# proprj_esp_s3_crokpocket_2025-06-12.net
KiCad netlist of a schematic drawn in EasyEDA Pro
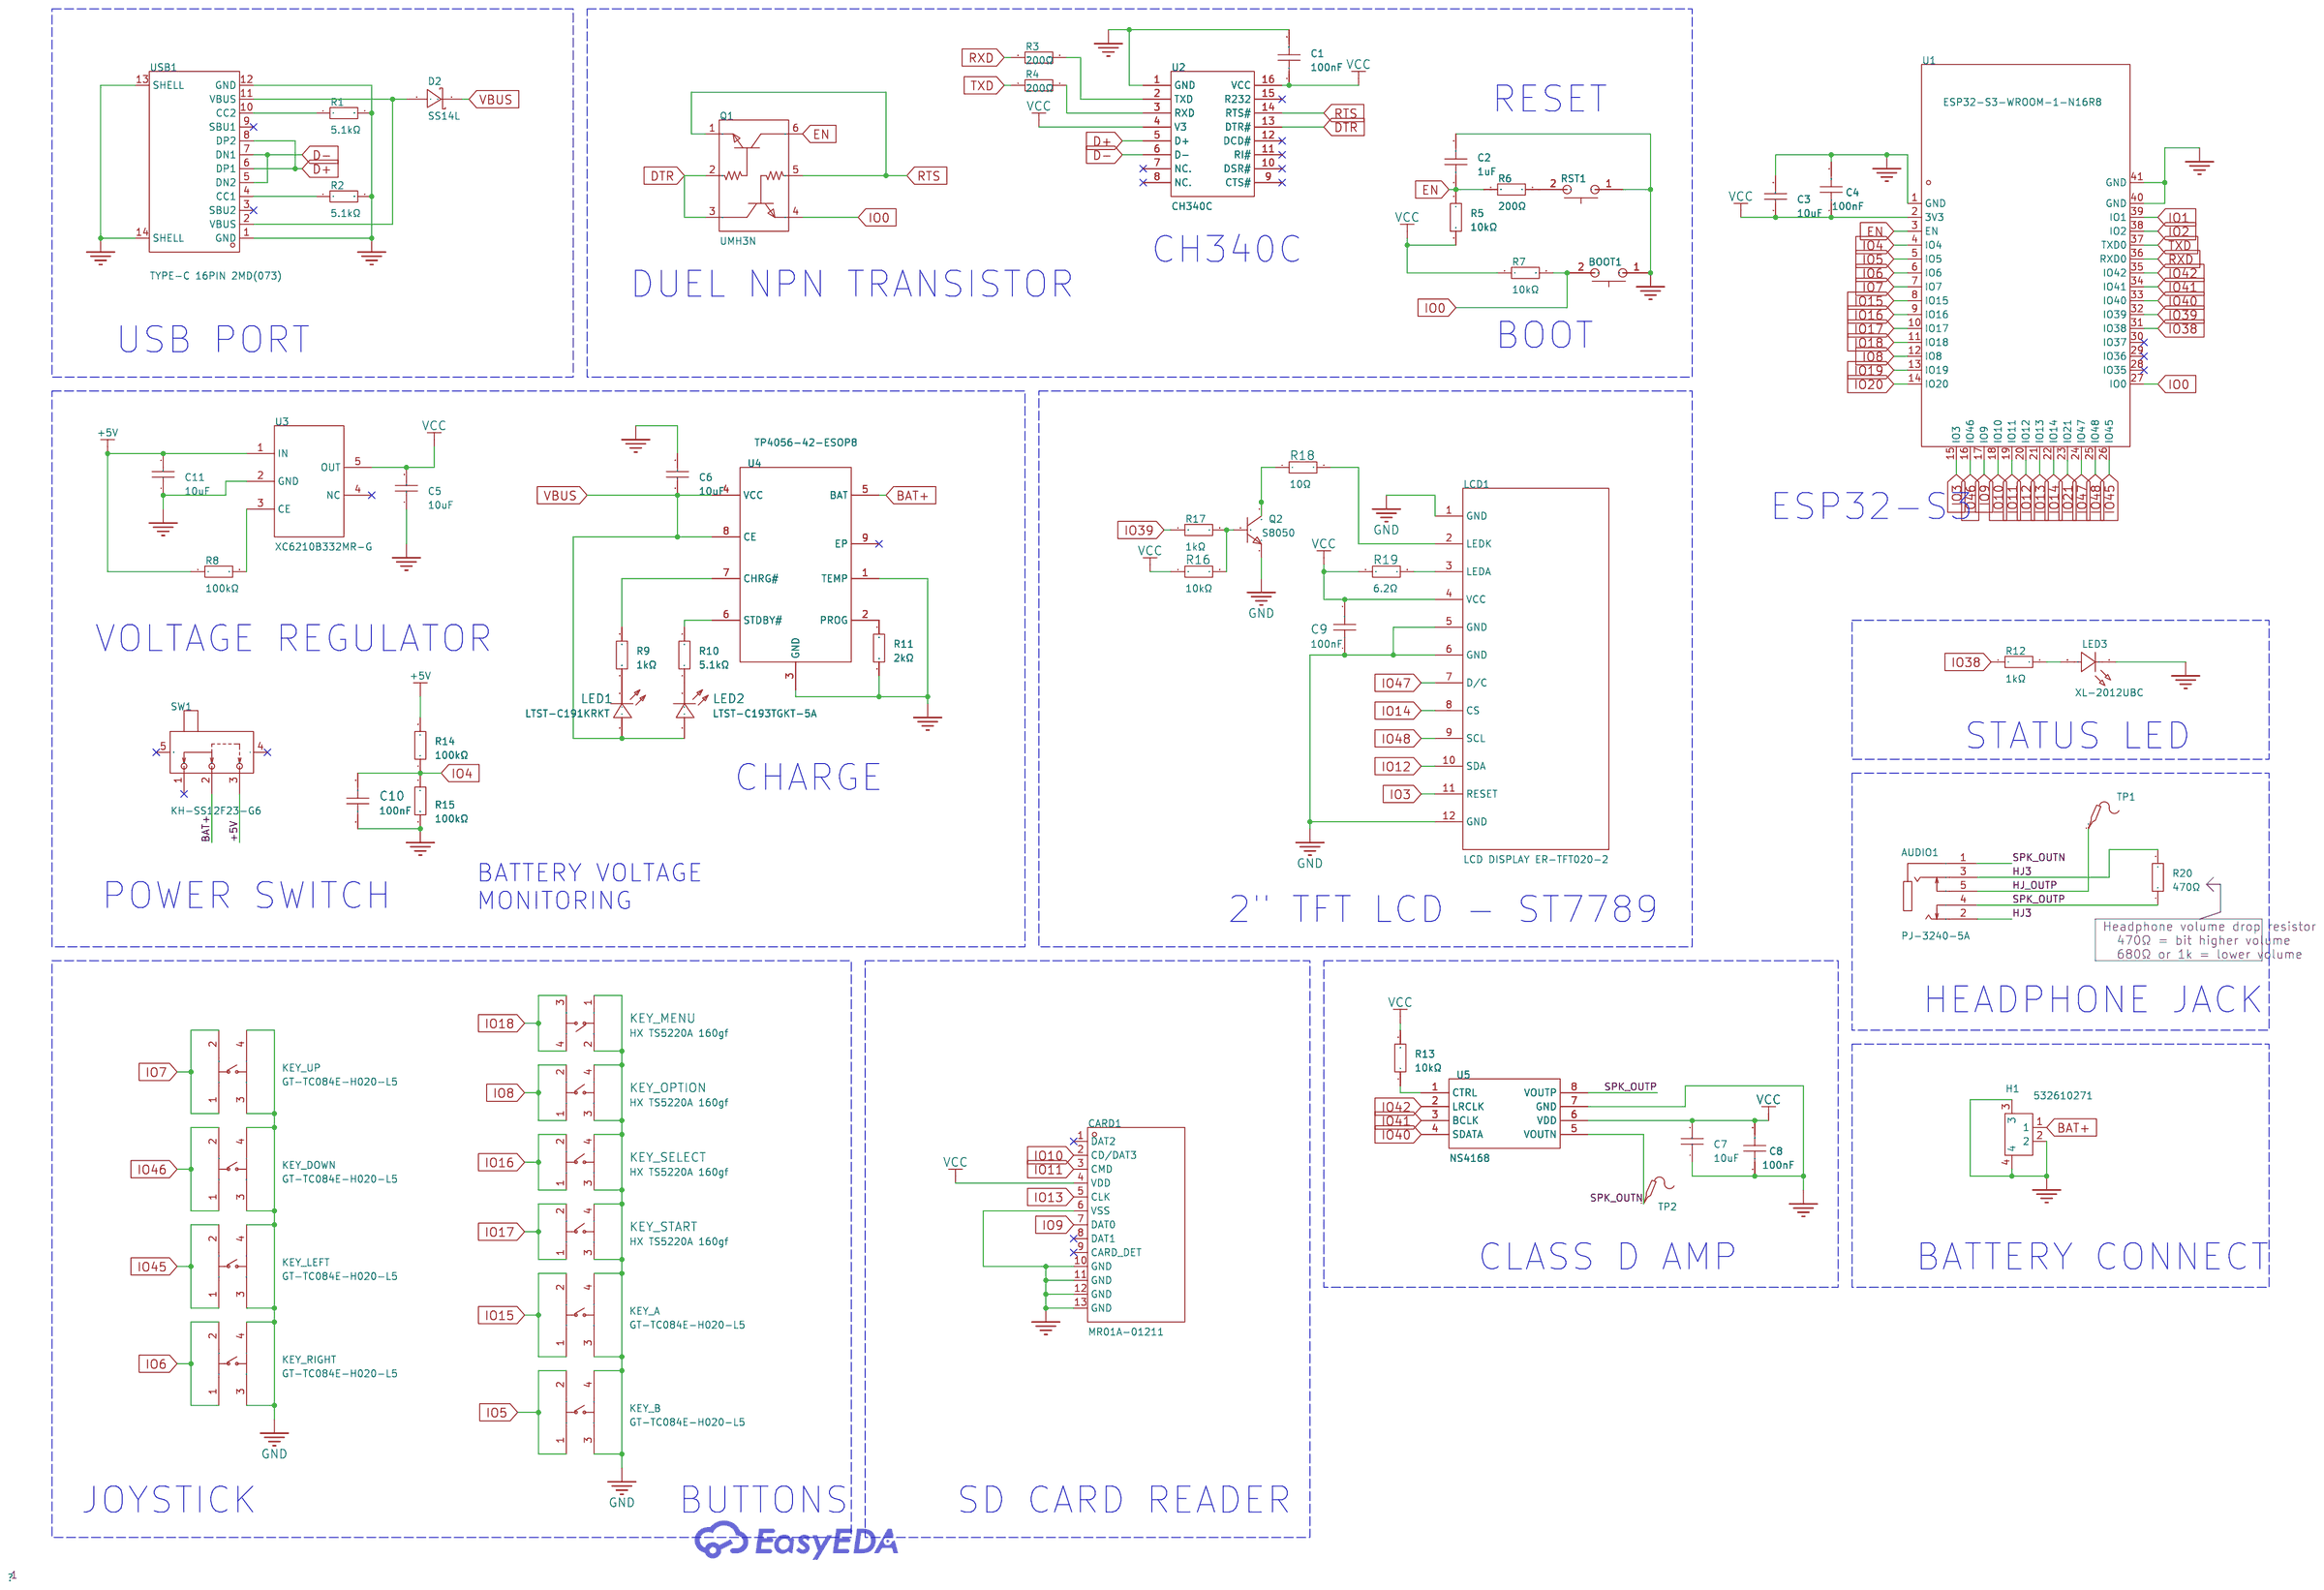
[diagram p0: schematic sheet]

(export (version "E")
  (design (tool "Eeschema 10.0.6"))
  (components
    (comp (ref "AUDIO1")
      (value "PJ-3240-5A")
      (footprint "easyedapro:AUDIO-TH_PJ-3240-5A")
      (description "Connector Type:3.5mm耳机座 Current Rating (Max):500mA Voltage Rating (Max):30V")
      (fields (field (name "Manufacturer") "韩国韩荣"))
      (libsource (lib "easyedapro") (part "PJ-3240-5A"))
    )
    (comp (ref "BOOT1")
      (value "GT-TC029B-H025-L1N")
      (footprint "easyedapro:SW-SMD_L3.9-W3.0-P4.45")
      (description "触点电流:50mA;额定电压(DC):12V;绝缘电阻:100MΩ;电路结构:单刀单掷;安装方式:立贴;带灯:无;作用力:250gf@±30gf;机械寿命:10万次;带支架:否;")
      (fields (field (name "Manufacturer") "G-Switch(品赞)"))
      (libsource (lib "easyedapro") (part "GT-TC029B-H025-L1N"))
    )
    (comp (ref "C1")
      (value "100nF")
      (footprint "easyedapro:C0603")
      (description "容值:100nF;精度:±10%;额定电压:50V;材质(温度系数):X7R;")
      (fields
        (field (name "Manufacturer Part") "CC0603KRX7R9BB104")
        (field (name "Manufacturer") "YAGEO(国巨)")
      )
      (libsource (lib "easyedapro") (part "CC0603KRX7R9BB104"))
    )
    (comp (ref "C2")
      (value "1uF")
      (footprint "easyedapro:C0603")
      (fields
        (field (name "Manufacturer Part") "CL10B105KA8NNNC")
        (field (name "Manufacturer") "SAMSUNG(三星)")
      )
      (libsource (lib "easyedapro") (part "CL10A105KB8NNNC"))
    )
    (comp (ref "C3")
      (value "10uF")
      (footprint "easyedapro:C0805")
      (fields
        (field (name "Manufacturer Part") "CL21B106KPQNNNE")
        (field (name "Manufacturer") "SAMSUNG(三星)")
      )
      (libsource (lib "easyedapro") (part "CL21B106KPQNNNE"))
    )
    (comp (ref "C4")
      (value "100nF")
      (footprint "easyedapro:C0603")
      (description "容值:100nF;精度:±10%;额定电压:50V;材质(温度系数):X7R;")
      (fields
        (field (name "Manufacturer Part") "CC0603KRX7R9BB104")
        (field (name "Manufacturer") "YAGEO(国巨)")
      )
      (libsource (lib "easyedapro") (part "CC0603KRX7R9BB104"))
    )
    (comp (ref "C5")
      (value "10uF")
      (footprint "easyedapro:C0805")
      (fields
        (field (name "Manufacturer Part") "CL21B106KPQNNNE")
        (field (name "Manufacturer") "SAMSUNG(三星)")
      )
      (libsource (lib "easyedapro") (part "CL21B106KPQNNNE"))
    )
    (comp (ref "C6")
      (value "10uF")
      (footprint "easyedapro:C0805")
      (fields
        (field (name "Manufacturer Part") "CL21B106KPQNNNE")
        (field (name "Manufacturer") "SAMSUNG(三星)")
      )
      (libsource (lib "easyedapro") (part "CL21B106KPQNNNE"))
    )
    (comp (ref "C7")
      (value "10uF")
      (footprint "easyedapro:C0805")
      (fields
        (field (name "Manufacturer Part") "CL21B106KPQNNNE")
        (field (name "Manufacturer") "SAMSUNG(三星)")
      )
      (libsource (lib "easyedapro") (part "CL21B106KPQNNNE"))
    )
    (comp (ref "C8")
      (value "100nF")
      (footprint "easyedapro:C0603")
      (description "容值:100nF;精度:±10%;额定电压:50V;材质(温度系数):X7R;")
      (fields
        (field (name "Manufacturer Part") "CC0603KRX7R9BB104")
        (field (name "Manufacturer") "YAGEO(国巨)")
      )
      (libsource (lib "easyedapro") (part "CC0603KRX7R9BB104"))
    )
    (comp (ref "C9")
      (value "100nF")
      (footprint "easyedapro:C0603")
      (fields
        (field (name "Manufacturer Part") "CC0603KRX7R9BB104")
        (field (name "Manufacturer") "YAGEO(国巨)")
      )
      (libsource (lib "") (part "CC0603KRX7R9BB104_1"))
    )
    (comp (ref "C10")
      (value "100nF")
      (footprint "easyedapro:C0603")
      (fields
        (field (name "Manufacturer Part") "CC0603KRX7R9BB104")
        (field (name "Manufacturer") "YAGEO(国巨)")
      )
      (libsource (lib "") (part "CC0603KRX7R9BB104_1"))
    )
    (comp (ref "C11")
      (value "10uF")
      (footprint "easyedapro:C0805")
      (fields
        (field (name "Manufacturer Part") "CL21B106KPQNNNE")
        (field (name "Manufacturer") "SAMSUNG(三星)")
      )
      (libsource (lib "easyedapro") (part "CL21B106KPQNNNE"))
    )
    (comp (ref "CARD1")
      (value "MR01A-01211")
      (footprint "easyedapro:TF-SMD_MR01A-01211")
      (description "卡类型:MicroSD卡(TF卡);连接器类型:卡座;卡连接方式:自弹式;本体最大高度:1.85mm;工作温度范围:-25°C~+85°C;")
      (fields (field (name "Manufacturer") "ATOM(爱特姆)"))
      (libsource (lib "easyedapro") (part "MR01A-01211"))
    )
    (comp (ref "D2")
      (value "SS14L")
      (footprint "easyedapro:SOD-123F_L2.8-W1.8-LS3.7-RD")
      (description "直流反向耐压(Vr):40V;平均整流电流(Io):1A;正向压降(Vf):550mV 1A;")
      (fields (field (name "Manufacturer") "Hottech(合科泰)"))
      (libsource (lib "easyedapro") (part "SS14L_C190475"))
    )
    (comp (ref "H1")
      (value "532610271")
      (footprint "easyedapro:CONN-SMD_532610271")
      (fields (field (name "Manufacturer") "MOLEX"))
      (libsource (lib "easyedapro") (part "532610271_C177225"))
    )
    (comp (ref "KEY_A")
      (value "GT-TC084E-H020-L5")
      (footprint "easyedapro:SW-SMD_4P-L5.2-W5.2-P3.70-LS6.4")
      (fields (field (name "Manufacturer") "G-Switch(品赞)"))
      (libsource (lib "easyedapro") (part "GT-TC084E-H020-L5"))
    )
    (comp (ref "KEY_B")
      (value "GT-TC084E-H020-L5")
      (footprint "easyedapro:SW-SMD_4P-L5.2-W5.2-P3.70-LS6.4")
      (fields (field (name "Manufacturer") "G-Switch(品赞)"))
      (libsource (lib "easyedapro") (part "GT-TC084E-H020-L5"))
    )
    (comp (ref "KEY_DOWN")
      (value "GT-TC084E-H020-L5")
      (footprint "easyedapro:SW-SMD_4P-L5.2-W5.2-P3.70-LS6.4")
      (fields (field (name "Manufacturer") "G-Switch(品赞)"))
      (libsource (lib "easyedapro") (part "GT-TC084E-H020-L5"))
    )
    (comp (ref "KEY_LEFT")
      (value "GT-TC084E-H020-L5")
      (footprint "easyedapro:SW-SMD_4P-L5.2-W5.2-P3.70-LS6.4")
      (fields (field (name "Manufacturer") "G-Switch(品赞)"))
      (libsource (lib "easyedapro") (part "GT-TC084E-H020-L5"))
    )
    (comp (ref "KEY_MENU")
      (value "HX TS5220A 160gf")
      (footprint "easyedapro:SW-SMD_4P-L5.2-W5.2-P3.70-LS6.4")
      (fields (field (name "Manufacturer") "hanxia(韩下)"))
      (libsource (lib "easyedapro") (part "HX TS5220A 160GF"))
    )
    (comp (ref "KEY_OPTION")
      (value "HX TS5220A 160gf")
      (footprint "easyedapro:SW-SMD_4P-L5.2-W5.2-P3.70-LS6.4")
      (fields (field (name "Manufacturer") "hanxia(韩下)"))
      (libsource (lib "easyedapro") (part "HX TS5220A 160GF"))
    )
    (comp (ref "KEY_RIGHT")
      (value "GT-TC084E-H020-L5")
      (footprint "easyedapro:SW-SMD_4P-L5.2-W5.2-P3.70-LS6.4")
      (fields (field (name "Manufacturer") "G-Switch(品赞)"))
      (libsource (lib "easyedapro") (part "GT-TC084E-H020-L5"))
    )
    (comp (ref "KEY_SELECT")
      (value "HX TS5220A 160gf")
      (footprint "easyedapro:SW-SMD_4P-L5.2-W5.2-P3.70-LS6.4")
      (fields (field (name "Manufacturer") "hanxia(韩下)"))
      (libsource (lib "easyedapro") (part "HX TS5220A 160GF"))
    )
    (comp (ref "KEY_START")
      (value "HX TS5220A 160gf")
      (footprint "easyedapro:SW-SMD_4P-L5.2-W5.2-P3.70-LS6.4")
      (fields (field (name "Manufacturer") "hanxia(韩下)"))
      (libsource (lib "easyedapro") (part "HX TS5220A 160GF"))
    )
    (comp (ref "KEY_UP")
      (value "GT-TC084E-H020-L5")
      (footprint "easyedapro:SW-SMD_4P-L5.2-W5.2-P3.70-LS6.4")
      (fields (field (name "Manufacturer") "G-Switch(品赞)"))
      (libsource (lib "easyedapro") (part "GT-TC084E-H020-L5"))
    )
    (comp (ref "LCD1")
      (value "LCD DISPLAY ER-TFT020-2")
      (fields (field (name "Manufacturer Part") "ER-TFT020-2") (field (name "Manufacturer") "EastRising"))
      (libsource (lib "easyedapro") (part "LCD DISPLAY ER-TFT020-2"))
    )
    (comp (ref "LED1")
      (value "LTST-C191KRKT")
      (footprint "easyedapro:LED0603-RD")
      (fields (field (name "Manufacturer") "LITEON(光宝)"))
      (libsource (lib "easyedapro") (part "LTST-C191KRKT"))
    )
    (comp (ref "LED2")
      (value "LTST-C193TGKT-5A")
      (footprint "easyedapro:LED0603-RD")
      (fields (field (name "Manufacturer") "LITEON(光宝)"))
      (libsource (lib "easyedapro") (part "LTST-C193TGKT-5A"))
    )
    (comp (ref "LED3")
      (value "XL-2012UBC")
      (footprint "easyedapro:LED0805-RD")
      (description "发光颜色:蓝色;功率:80mW;正向电流:25mA;主波长:460nm~469nm;透镜颜色:无色透明透镜;色温:-;发光角度:120°;载带方式:正贴;工作温度:-30°C~+85°C;")
      (fields (field (name "Manufacturer") "XINGLIGHT(成兴光)"))
      (libsource (lib "easyedapro") (part "XL-2012UBC"))
    )
    (comp (ref "Q1")
      (value "UMH3N")
      (footprint "easyedapro:SC-70-6_L2.2-W1.3-P0.65-LS2.1-BR")
      (description "晶体管类型:2个NPN-预偏置;功率(Pd):150mW;集电极电流(Ic):100mA;集射极击穿电压(Vceo):50V;")
      (fields (field (name "Manufacturer") "CJ(江苏长电/长晶)"))
      (libsource (lib "easyedapro") (part "UMH3N"))
    )
    (comp (ref "Q2")
      (value "S8050")
      (footprint "easyedapro:SOT-23-3_L2.9-W1.6-P1.90-LS2.8-BR")
      (fields (field (name "Manufacturer") "Hottech(合科泰)"))
      (libsource (lib "easyedapro") (part "S8050_C181158"))
    )
    (comp (ref "R1")
      (value "5.1kΩ")
      (footprint "easyedapro:R0603")
      (description "电阻类型:厚膜电阻;阻值:5.1kΩ;精度:±1%;功率:100mW;最大工作电压:75V;温度系数:±100ppm/°C;")
      (fields
        (field (name "Manufacturer Part") "0603WAF5101T5E")
        (field (name "Manufacturer") "UNI-ROYAL(厚声)")
      )
      (libsource (lib "easyedapro") (part "0603WAF5101T5E"))
    )
    (comp (ref "R2")
      (value "5.1kΩ")
      (footprint "easyedapro:R0603")
      (description "电阻类型:厚膜电阻;阻值:5.1kΩ;精度:±1%;功率:100mW;最大工作电压:75V;温度系数:±100ppm/°C;")
      (fields
        (field (name "Manufacturer Part") "0603WAF5101T5E")
        (field (name "Manufacturer") "UNI-ROYAL(厚声)")
      )
      (libsource (lib "easyedapro") (part "0603WAF5101T5E"))
    )
    (comp (ref "R3")
      (value "200Ω")
      (footprint "easyedapro:R0603")
      (description "电阻类型:厚膜电阻;阻值:200Ω;精度:±1%;功率:100mW;最大工作电压:75V;温度系数:±100ppm/°C;")
      (fields
        (field (name "Manufacturer Part") "0603WAF2000T5E")
        (field (name "Manufacturer") "UNI-ROYAL(厚声)")
      )
      (libsource (lib "easyedapro") (part "0603WAF2000T5E"))
    )
    (comp (ref "R4")
      (value "200Ω")
      (footprint "easyedapro:R0603")
      (description "电阻类型:厚膜电阻;阻值:200Ω;精度:±1%;功率:100mW;最大工作电压:75V;温度系数:±100ppm/°C;")
      (fields
        (field (name "Manufacturer Part") "0603WAF2000T5E")
        (field (name "Manufacturer") "UNI-ROYAL(厚声)")
      )
      (libsource (lib "easyedapro") (part "0603WAF2000T5E"))
    )
    (comp (ref "R5")
      (value "10kΩ")
      (footprint "easyedapro:R0603")
      (description "电阻类型:厚膜电阻;阻值:10kΩ;精度:±1%;功率:100mW;最大工作电压:75V;温度系数:±100ppm/°C;")
      (fields
        (field (name "Manufacturer Part") "0603WAF1002T5E")
        (field (name "Manufacturer") "UNI-ROYAL(厚声)")
      )
      (libsource (lib "") (part "0603WAF1002T5E_1"))
    )
    (comp (ref "R6")
      (value "200Ω")
      (footprint "easyedapro:R0603")
      (description "电阻类型:厚膜电阻;阻值:200Ω;精度:±1%;功率:100mW;最大工作电压:75V;温度系数:±100ppm/°C;")
      (fields
        (field (name "Manufacturer Part") "0603WAF2000T5E")
        (field (name "Manufacturer") "UNI-ROYAL(厚声)")
      )
      (libsource (lib "easyedapro") (part "0603WAF2000T5E"))
    )
    (comp (ref "R7")
      (value "10kΩ")
      (footprint "easyedapro:R0603")
      (description "电阻类型:厚膜电阻;阻值:10kΩ;精度:±1%;功率:100mW;最大工作电压:75V;温度系数:±100ppm/°C;")
      (fields
        (field (name "Manufacturer Part") "0603WAF1002T5E")
        (field (name "Manufacturer") "UNI-ROYAL(厚声)")
      )
      (libsource (lib "") (part "0603WAF1002T5E_1"))
    )
    (comp (ref "R8")
      (value "100kΩ")
      (footprint "easyedapro:R0603")
      (fields
        (field (name "Manufacturer Part") "0603WAF1003T5E")
        (field (name "Manufacturer") "UNI-ROYAL(厚声)")
      )
      (libsource (lib "easyedapro") (part "0603WAF1003T5E"))
    )
    (comp (ref "R9")
      (value "1kΩ")
      (footprint "easyedapro:R0603")
      (description "电阻类型:厚膜电阻;阻值:1kΩ;精度:±1%;功率:100mW;最大工作电压:75V;温度系数:±100ppm/°C;")
      (fields
        (field (name "Manufacturer Part") "0603WAF1001T5E")
        (field (name "Manufacturer") "UNI-ROYAL(厚声)")
      )
      (libsource (lib "easyedapro") (part "0603WAF1001T5E"))
    )
    (comp (ref "R10")
      (value "5.1kΩ")
      (footprint "easyedapro:R0603")
      (fields
        (field (name "Manufacturer Part") "0603WAF5101T5E")
        (field (name "Manufacturer") "UNI-ROYAL(厚声)")
      )
      (libsource (lib "easyedapro") (part "0603WAF5101T5E"))
    )
    (comp (ref "R11")
      (value "2kΩ")
      (footprint "easyedapro:R0603")
      (description "电阻类型:厚膜电阻;阻值:2kΩ;精度:±1%;功率:100mW;最大工作电压:75V;温度系数:±100ppm/°C;")
      (fields
        (field (name "Manufacturer Part") "0603WAF2001T5E")
        (field (name "Manufacturer") "UNI-ROYAL(厚声)")
      )
      (libsource (lib "easyedapro") (part "0603WAF2001T5E"))
    )
    (comp (ref "R12")
      (value "1kΩ")
      (footprint "easyedapro:R0603")
      (description "电阻类型:厚膜电阻;阻值:1kΩ;精度:±1%;功率:100mW;最大工作电压:75V;温度系数:±100ppm/°C;")
      (fields
        (field (name "Manufacturer Part") "0603WAF1001T5E")
        (field (name "Manufacturer") "UNI-ROYAL(厚声)")
      )
      (libsource (lib "easyedapro") (part "0603WAF1001T5E"))
    )
    (comp (ref "R13")
      (value "10kΩ")
      (footprint "easyedapro:R0603")
      (description "电阻类型:厚膜电阻;阻值:10kΩ;精度:±1%;功率:100mW;最大工作电压:75V;温度系数:±100ppm/°C;")
      (fields
        (field (name "Manufacturer Part") "0603WAF1002T5E")
        (field (name "Manufacturer") "UNI-ROYAL(厚声)")
      )
      (libsource (lib "") (part "0603WAF1002T5E_1"))
    )
    (comp (ref "R14")
      (value "100kΩ")
      (footprint "easyedapro:R0603")
      (fields
        (field (name "Manufacturer Part") "0603WAF1003T5E")
        (field (name "Manufacturer") "UNI-ROYAL(厚声)")
      )
      (libsource (lib "easyedapro") (part "0603WAF1003T5E"))
    )
    (comp (ref "R15")
      (value "100kΩ")
      (footprint "easyedapro:R0603")
      (fields
        (field (name "Manufacturer Part") "0603WAF1003T5E")
        (field (name "Manufacturer") "UNI-ROYAL(厚声)")
      )
      (libsource (lib "easyedapro") (part "0603WAF1003T5E"))
    )
    (comp (ref "R16")
      (value "10kΩ")
      (footprint "easyedapro:R0603")
      (fields
        (field (name "Manufacturer Part") "0603WAF1002T5E")
        (field (name "Manufacturer") "UNI-ROYAL(厚声)")
      )
      (libsource (lib "easyedapro") (part "0603WAF1002T5E"))
    )
    (comp (ref "R17")
      (value "1kΩ")
      (footprint "easyedapro:R0603")
      (fields
        (field (name "Manufacturer Part") "0603WAF1001T5E")
        (field (name "Manufacturer") "UNI-ROYAL(厚声)")
      )
      (libsource (lib "easyedapro") (part "0603WAF1001T5E"))
    )
    (comp (ref "R18")
      (value "10Ω")
      (footprint "easyedapro:R0603")
      (fields
        (field (name "Manufacturer Part") "0603WAF100JT5E")
        (field (name "Manufacturer") "UNI-ROYAL(厚声)")
      )
      (libsource (lib "easyedapro") (part "0603WAF100JT5E"))
    )
    (comp (ref "R19")
      (value "6.2Ω")
      (footprint "easyedapro:R0603")
      (fields
        (field (name "Manufacturer Part") "0603WAF620KT5E")
        (field (name "Manufacturer") "UNI-ROYAL(厚声)")
      )
      (libsource (lib "easyedapro") (part "0603WAF620KT5E"))
    )
    (comp (ref "R20")
      (value "470Ω")
      (footprint "easyedapro:R0603")
      (fields
        (field (name "Manufacturer Part") "0603WAF4700T5E")
        (field (name "Manufacturer") "UNI-ROYAL(厚声)")
      )
      (libsource (lib "easyedapro") (part "0603WAF4700T5E"))
    )
    (comp (ref "RST1")
      (value "GT-TC029B-H025-L1N")
      (footprint "easyedapro:SW-SMD_L3.9-W3.0-P4.45")
      (description "触点电流:50mA;额定电压(DC):12V;绝缘电阻:100MΩ;电路结构:单刀单掷;安装方式:立贴;带灯:无;作用力:250gf@±30gf;机械寿命:10万次;带支架:否;")
      (fields (field (name "Manufacturer") "G-Switch(品赞)"))
      (libsource (lib "easyedapro") (part "GT-TC029B-H025-L1N"))
    )
    (comp (ref "SW1")
      (value "KH-SS12F23-G6")
      (footprint "easyedapro:SW-TH_KH-SS12F23-G6")
      (fields (field (name "Manufacturer") "kinghelm(金航标)"))
      (libsource (lib "easyedapro") (part "KH-SS12F23-G6"))
    )
    (comp (ref "TP1")
      (value "~")
      (footprint "easyedapro:Test-Point-0.5mm")
      (description "Test Point 测试点")
      (libsource (lib "easyedapro") (part "Test-Point"))
    )
    (comp (ref "TP2")
      (value "~")
      (footprint "easyedapro:Test-Point-0.5mm")
      (description "Test Point 测试点")
      (libsource (lib "easyedapro") (part "Test-Point"))
    )
    (comp (ref "U1")
      (value "ESP32-S3-WROOM-1-N16R8")
      (footprint "easyedapro:WIRELM-SMD_ESP32-S3-WROOM-1")
      (fields (field (name "Manufacturer") "ESPRESSIF(乐鑫)"))
      (libsource (lib "easyedapro") (part "ESP32-S3-WROOM-1(N16R8)"))
    )
    (comp (ref "U2")
      (value "CH340C")
      (fields (field (name "Manufacturer") "WCH(南京沁恒)"))
      (libsource (lib "easyedapro") (part "CH340C"))
    )
    (comp (ref "U3")
      (value "XC6210B332MR-G")
      (footprint "easyedapro:SOT-23-5_L3.0-W1.7-P0.95-LS2.8-BR")
      (fields (field (name "Manufacturer") "TOREX(特瑞仕)"))
      (libsource (lib "easyedapro") (part "XC6210B332MR"))
    )
    (comp (ref "U4")
      (value "TP4056-42-ESOP8")
      (footprint "easyedapro:ESOP-8_L4.9-W3.9-P1.27-LS6.0-BL-EP")
      (fields (field (name "Manufacturer") "TOPPOWER(南京拓微)"))
      (libsource (lib "easyedapro") (part "TP4056"))
    )
    (comp (ref "U5")
      (value "NS4168")
      (footprint "easyedapro:ESOP-8_L4.9-W3.9-P1.27-LS6.0-BL-EP-1")
      (description "NS4168 2.5W I2S数字输入单声道D类音频功率放大器功放芯片IC")
      (libsource (lib "easyedapro") (part "NS4168"))
    )
    (comp (ref "USB1")
      (value "TYPE-C 16PIN 2MD(073)")
      (footprint "easyedapro:USB-C-SMD_TYPE-C-6PIN-2MD-073")
      (description "连接器类型:Type-C;标准:-;公母:母座;触点数量:16;端口数量:1;安装方式:卧贴;额定电流 - 电源:5A;工作温度范围:-25°C~+85°C;")
      (fields (field (name "Manufacturer") "SHOU HAN(首韩)"))
      (libsource (lib "easyedapro") (part "TYPE-C 16PIN 2MD(073)"))
    )
  )
  (nets
    (net (code "1") (name "+5V") (class "Default")
      (node (ref "C11") (pin "2") (pinfunction "2_2") (pintype "input"))
      (node (ref "R14") (pin "2") (pinfunction "2_2") (pintype "input"))
      (node (ref "R8") (pin "1") (pinfunction "1_1") (pintype "input"))
      (node (ref "SW1") (pin "3") (pinfunction "3_3") (pintype "unspecified"))
      (node (ref "U3") (pin "1") (pinfunction "IN_1") (pintype "unspecified"))
    )
    (net (code "2") (name "/HJ3") (class "Default")
      (node (ref "AUDIO1") (pin "2") (pinfunction "2_2") (pintype "unspecified"))
      (node (ref "AUDIO1") (pin "3") (pinfunction "3_3") (pintype "unspecified"))
      (node (ref "R20") (pin "2") (pinfunction "2_2") (pintype "input"))
    )
    (net (code "3") (name "/HJ_OUTP") (class "Default")
      (node (ref "AUDIO1") (pin "5") (pinfunction "5_5") (pintype "unspecified"))
      (node (ref "TP1") (pin "1") (pinfunction "1_1") (pintype "input"))
    )
    (net (code "4") (name "/SPK_OUTN") (class "Default")
      (node (ref "AUDIO1") (pin "1") (pinfunction "1_1") (pintype "unspecified"))
      (node (ref "TP2") (pin "1") (pinfunction "1_1") (pintype "input"))
      (node (ref "U5") (pin "5") (pinfunction "VOUTN_5") (pintype "input"))
    )
    (net (code "5") (name "/SPK_OUTP") (class "Default")
      (node (ref "AUDIO1") (pin "4") (pinfunction "4_4") (pintype "unspecified"))
      (node (ref "R20") (pin "1") (pinfunction "1_1") (pintype "input"))
      (node (ref "U5") (pin "8") (pinfunction "VOUTP_8") (pintype "input"))
    )
    (net (code "6") (name "BAT+") (class "Default")
      (node (ref "H1") (pin "1") (pinfunction "1_1") (pintype "unspecified"))
      (node (ref "SW1") (pin "2") (pinfunction "2_2") (pintype "unspecified"))
      (node (ref "U4") (pin "5") (pinfunction "BAT_5") (pintype "unspecified"))
    )
    (net (code "7") (name "D+") (class "Default")
      (node (ref "U2") (pin "5") (pinfunction "D+_5") (pintype "input"))
      (node (ref "USB1") (pin "6") (pinfunction "DP1_6") (pintype "input"))
      (node (ref "USB1") (pin "8") (pinfunction "DP2_8") (pintype "input"))
    )
    (net (code "8") (name "D-") (class "Default")
      (node (ref "U2") (pin "6") (pinfunction "D-_6") (pintype "input"))
      (node (ref "USB1") (pin "5") (pinfunction "DN2_5") (pintype "input"))
      (node (ref "USB1") (pin "7") (pinfunction "DN1_7") (pintype "input"))
    )
    (net (code "9") (name "DTR") (class "Default")
      (node (ref "Q1") (pin "2") (pinfunction "B_2") (pintype "input"))
      (node (ref "Q1") (pin "3") (pinfunction "C_3") (pintype "input"))
      (node (ref "U2") (pin "13") (pinfunction "DTR#_13") (pintype "input"))
    )
    (net (code "10") (name "EN") (class "Default")
      (node (ref "C2") (pin "1") (pinfunction "1_1") (pintype "unspecified"))
      (node (ref "Q1") (pin "6") (pinfunction "C_6") (pintype "input"))
      (node (ref "R5") (pin "1") (pinfunction "1_1") (pintype "input"))
      (node (ref "R6") (pin "2") (pinfunction "2_2") (pintype "input"))
      (node (ref "U1") (pin "3") (pinfunction "EN_3") (pintype "input"))
    )
    (net (code "11") (name "GND") (class "Default")
      (node (ref "BOOT1") (pin "1") (pinfunction "1_1") (pintype "input"))
      (node (ref "C1") (pin "2") (pinfunction "2_2") (pintype "unspecified"))
      (node (ref "C10") (pin "2") (pinfunction "2_2") (pintype "input"))
      (node (ref "C11") (pin "1") (pinfunction "1_1") (pintype "input"))
      (node (ref "C2") (pin "2") (pinfunction "2_2") (pintype "unspecified"))
      (node (ref "C3") (pin "2") (pinfunction "2_2") (pintype "input"))
      (node (ref "C4") (pin "2") (pinfunction "2_2") (pintype "unspecified"))
      (node (ref "C5") (pin "1") (pinfunction "1_1") (pintype "input"))
      (node (ref "C6") (pin "2") (pinfunction "2_2") (pintype "input"))
      (node (ref "C7") (pin "1") (pinfunction "1_1") (pintype "input"))
      (node (ref "C8") (pin "1") (pinfunction "1_1") (pintype "unspecified"))
      (node (ref "C9") (pin "1") (pinfunction "1_1") (pintype "input"))
      (node (ref "CARD1") (pin "10") (pinfunction "GND_10") (pintype "input"))
      (node (ref "CARD1") (pin "11") (pinfunction "GND_11") (pintype "input"))
      (node (ref "CARD1") (pin "12") (pinfunction "GND_12") (pintype "input"))
      (node (ref "CARD1") (pin "13") (pinfunction "GND_13") (pintype "input"))
      (node (ref "CARD1") (pin "6") (pinfunction "VSS_6") (pintype "input"))
      (node (ref "H1") (pin "2") (pinfunction "2_2") (pintype "unspecified"))
      (node (ref "H1") (pin "3") (pinfunction "3_3") (pintype "unspecified"))
      (node (ref "H1") (pin "4") (pinfunction "4_4") (pintype "unspecified"))
      (node (ref "KEY_A") (pin "3") (pinfunction "3_3") (pintype "unspecified"))
      (node (ref "KEY_A") (pin "4") (pinfunction "4_4") (pintype "unspecified"))
      (node (ref "KEY_B") (pin "3") (pinfunction "3_3") (pintype "unspecified"))
      (node (ref "KEY_B") (pin "4") (pinfunction "4_4") (pintype "unspecified"))
      (node (ref "KEY_DOWN") (pin "3") (pinfunction "3_3") (pintype "unspecified"))
      (node (ref "KEY_DOWN") (pin "4") (pinfunction "4_4") (pintype "unspecified"))
      (node (ref "KEY_LEFT") (pin "3") (pinfunction "3_3") (pintype "unspecified"))
      (node (ref "KEY_LEFT") (pin "4") (pinfunction "4_4") (pintype "unspecified"))
      (node (ref "KEY_MENU") (pin "1") (pinfunction "1_1") (pintype "input"))
      (node (ref "KEY_MENU") (pin "2") (pinfunction "2_2") (pintype "input"))
      (node (ref "KEY_OPTION") (pin "3") (pinfunction "3_3") (pintype "input"))
      (node (ref "KEY_OPTION") (pin "4") (pinfunction "4_4") (pintype "input"))
      (node (ref "KEY_RIGHT") (pin "3") (pinfunction "3_3") (pintype "unspecified"))
      (node (ref "KEY_RIGHT") (pin "4") (pinfunction "4_4") (pintype "unspecified"))
      (node (ref "KEY_SELECT") (pin "3") (pinfunction "3_3") (pintype "input"))
      (node (ref "KEY_SELECT") (pin "4") (pinfunction "4_4") (pintype "input"))
      (node (ref "KEY_START") (pin "3") (pinfunction "3_3") (pintype "input"))
      (node (ref "KEY_START") (pin "4") (pinfunction "4_4") (pintype "input"))
      (node (ref "KEY_UP") (pin "3") (pinfunction "3_3") (pintype "unspecified"))
      (node (ref "KEY_UP") (pin "4") (pinfunction "4_4") (pintype "unspecified"))
      (node (ref "LCD1") (pin "1") (pinfunction "GND_1") (pintype "unspecified"))
      (node (ref "LCD1") (pin "12") (pinfunction "GND_12") (pintype "unspecified"))
      (node (ref "LCD1") (pin "5") (pinfunction "GND_5") (pintype "unspecified"))
      (node (ref "LCD1") (pin "6") (pinfunction "GND_6") (pintype "unspecified"))
      (node (ref "LED3") (pin "1") (pinfunction "K_1") (pintype "unspecified"))
      (node (ref "Q2") (pin "2") (pinfunction "2_2") (pintype "input"))
      (node (ref "R1") (pin "2") (pinfunction "2_2") (pintype "input"))
      (node (ref "R11") (pin "1") (pinfunction "1_1") (pintype "input"))
      (node (ref "R15") (pin "2") (pinfunction "2_2") (pintype "input"))
      (node (ref "R2") (pin "2") (pinfunction "2_2") (pintype "input"))
      (node (ref "RST1") (pin "1") (pinfunction "1_1") (pintype "input"))
      (node (ref "U1") (pin "1") (pinfunction "GND_1") (pintype "input"))
      (node (ref "U1") (pin "40") (pinfunction "GND_40") (pintype "input"))
      (node (ref "U1") (pin "41") (pinfunction "GND_41") (pintype "input"))
      (node (ref "U2") (pin "1") (pinfunction "GND_1") (pintype "input"))
      (node (ref "U3") (pin "2") (pinfunction "GND_2") (pintype "unspecified"))
      (node (ref "U4") (pin "1") (pinfunction "TEMP_1") (pintype "unspecified"))
      (node (ref "U4") (pin "3") (pinfunction "GND_3") (pintype "unspecified"))
      (node (ref "U5") (pin "7") (pinfunction "GND_7") (pintype "input"))
      (node (ref "USB1") (pin "1") (pinfunction "GND_1") (pintype "input"))
      (node (ref "USB1") (pin "12") (pinfunction "GND_12") (pintype "input"))
      (node (ref "USB1") (pin "13") (pinfunction "SHELL_13") (pintype "input"))
      (node (ref "USB1") (pin "14") (pinfunction "SHELL_14") (pintype "input"))
    )
    (net (code "12") (name "IO0") (class "Default")
      (node (ref "BOOT1") (pin "2") (pinfunction "2_2") (pintype "input"))
      (node (ref "Q1") (pin "4") (pinfunction "E_4") (pintype "input"))
      (node (ref "R7") (pin "2") (pinfunction "2_2") (pintype "input"))
      (node (ref "U1") (pin "27") (pinfunction "IO0_27") (pintype "input"))
    )
    (net (code "13") (name "IO1") (class "Default")
      (node (ref "U1") (pin "39") (pinfunction "IO1_39") (pintype "input"))
    )
    (net (code "14") (name "IO2") (class "Default")
      (node (ref "U1") (pin "38") (pinfunction "IO2_38") (pintype "input"))
    )
    (net (code "15") (name "IO3") (class "Default")
      (node (ref "LCD1") (pin "11") (pinfunction "RESET_11") (pintype "unspecified"))
      (node (ref "U1") (pin "15") (pinfunction "IO3_15") (pintype "input"))
    )
    (net (code "16") (name "IO4") (class "Default")
      (node (ref "C10") (pin "1") (pinfunction "1_1") (pintype "input"))
      (node (ref "R14") (pin "1") (pinfunction "1_1") (pintype "input"))
      (node (ref "R15") (pin "1") (pinfunction "1_1") (pintype "input"))
      (node (ref "U1") (pin "4") (pinfunction "IO4_4") (pintype "input"))
    )
    (net (code "17") (name "IO5") (class "Default")
      (node (ref "KEY_B") (pin "1") (pinfunction "1_1") (pintype "unspecified"))
      (node (ref "KEY_B") (pin "2") (pinfunction "2_2") (pintype "unspecified"))
      (node (ref "U1") (pin "5") (pinfunction "IO5_5") (pintype "input"))
    )
    (net (code "18") (name "IO6") (class "Default")
      (node (ref "KEY_RIGHT") (pin "1") (pinfunction "1_1") (pintype "unspecified"))
      (node (ref "KEY_RIGHT") (pin "2") (pinfunction "2_2") (pintype "unspecified"))
      (node (ref "U1") (pin "6") (pinfunction "IO6_6") (pintype "input"))
    )
    (net (code "19") (name "IO7") (class "Default")
      (node (ref "KEY_UP") (pin "1") (pinfunction "1_1") (pintype "unspecified"))
      (node (ref "KEY_UP") (pin "2") (pinfunction "2_2") (pintype "unspecified"))
      (node (ref "U1") (pin "7") (pinfunction "IO7_7") (pintype "input"))
    )
    (net (code "20") (name "IO8") (class "Default")
      (node (ref "KEY_OPTION") (pin "1") (pinfunction "1_1") (pintype "input"))
      (node (ref "KEY_OPTION") (pin "2") (pinfunction "2_2") (pintype "input"))
      (node (ref "U1") (pin "12") (pinfunction "IO8_12") (pintype "input"))
    )
    (net (code "21") (name "IO9") (class "Default")
      (node (ref "CARD1") (pin "7") (pinfunction "DAT0_7") (pintype "input"))
      (node (ref "U1") (pin "17") (pinfunction "IO9_17") (pintype "input"))
    )
    (net (code "22") (name "IO10") (class "Default")
      (node (ref "CARD1") (pin "2") (pinfunction "CD/DAT3_2") (pintype "input"))
      (node (ref "U1") (pin "18") (pinfunction "IO10_18") (pintype "input"))
    )
    (net (code "23") (name "IO11") (class "Default")
      (node (ref "CARD1") (pin "3") (pinfunction "CMD_3") (pintype "input"))
      (node (ref "U1") (pin "19") (pinfunction "IO11_19") (pintype "input"))
    )
    (net (code "24") (name "IO12") (class "Default")
      (node (ref "LCD1") (pin "10") (pinfunction "SDA_10") (pintype "unspecified"))
      (node (ref "U1") (pin "20") (pinfunction "IO12_20") (pintype "input"))
    )
    (net (code "25") (name "IO13") (class "Default")
      (node (ref "CARD1") (pin "5") (pinfunction "CLK_5") (pintype "input"))
      (node (ref "U1") (pin "21") (pinfunction "IO13_21") (pintype "input"))
    )
    (net (code "26") (name "IO14") (class "Default")
      (node (ref "LCD1") (pin "8") (pinfunction "CS_8") (pintype "unspecified"))
      (node (ref "U1") (pin "22") (pinfunction "IO14_22") (pintype "input"))
    )
    (net (code "27") (name "IO15") (class "Default")
      (node (ref "KEY_A") (pin "1") (pinfunction "1_1") (pintype "unspecified"))
      (node (ref "KEY_A") (pin "2") (pinfunction "2_2") (pintype "unspecified"))
      (node (ref "U1") (pin "8") (pinfunction "IO15_8") (pintype "input"))
    )
    (net (code "28") (name "IO16") (class "Default")
      (node (ref "KEY_SELECT") (pin "1") (pinfunction "1_1") (pintype "input"))
      (node (ref "KEY_SELECT") (pin "2") (pinfunction "2_2") (pintype "input"))
      (node (ref "U1") (pin "9") (pinfunction "IO16_9") (pintype "input"))
    )
    (net (code "29") (name "IO17") (class "Default")
      (node (ref "KEY_START") (pin "1") (pinfunction "1_1") (pintype "input"))
      (node (ref "KEY_START") (pin "2") (pinfunction "2_2") (pintype "input"))
      (node (ref "U1") (pin "10") (pinfunction "IO17_10") (pintype "input"))
    )
    (net (code "30") (name "IO18") (class "Default")
      (node (ref "KEY_MENU") (pin "3") (pinfunction "3_3") (pintype "input"))
      (node (ref "KEY_MENU") (pin "4") (pinfunction "4_4") (pintype "input"))
      (node (ref "U1") (pin "11") (pinfunction "IO18_11") (pintype "input"))
    )
    (net (code "31") (name "IO19") (class "Default")
      (node (ref "U1") (pin "13") (pinfunction "IO19_13") (pintype "input"))
    )
    (net (code "32") (name "IO20") (class "Default")
      (node (ref "U1") (pin "14") (pinfunction "IO20_14") (pintype "input"))
    )
    (net (code "33") (name "IO21") (class "Default")
      (node (ref "U1") (pin "23") (pinfunction "IO21_23") (pintype "input"))
    )
    (net (code "34") (name "IO38") (class "Default")
      (node (ref "R12") (pin "1") (pinfunction "1_1") (pintype "input"))
      (node (ref "U1") (pin "31") (pinfunction "IO38_31") (pintype "input"))
    )
    (net (code "35") (name "IO39") (class "Default")
      (node (ref "R17") (pin "1") (pinfunction "1_1") (pintype "input"))
      (node (ref "U1") (pin "32") (pinfunction "IO39_32") (pintype "input"))
    )
    (net (code "36") (name "IO40") (class "Default")
      (node (ref "U1") (pin "33") (pinfunction "IO40_33") (pintype "input"))
      (node (ref "U5") (pin "4") (pinfunction "SDATA_4") (pintype "input"))
    )
    (net (code "37") (name "IO41") (class "Default")
      (node (ref "U1") (pin "34") (pinfunction "IO41_34") (pintype "input"))
      (node (ref "U5") (pin "3") (pinfunction "BCLK_3") (pintype "input"))
    )
    (net (code "38") (name "IO42") (class "Default")
      (node (ref "U1") (pin "35") (pinfunction "IO42_35") (pintype "input"))
      (node (ref "U5") (pin "2") (pinfunction "LRCLK_2") (pintype "input"))
    )
    (net (code "39") (name "IO45") (class "Default")
      (node (ref "KEY_LEFT") (pin "1") (pinfunction "1_1") (pintype "unspecified"))
      (node (ref "KEY_LEFT") (pin "2") (pinfunction "2_2") (pintype "unspecified"))
      (node (ref "U1") (pin "26") (pinfunction "IO45_26") (pintype "input"))
    )
    (net (code "40") (name "IO46") (class "Default")
      (node (ref "KEY_DOWN") (pin "1") (pinfunction "1_1") (pintype "unspecified"))
      (node (ref "KEY_DOWN") (pin "2") (pinfunction "2_2") (pintype "unspecified"))
      (node (ref "U1") (pin "16") (pinfunction "IO46_16") (pintype "input"))
    )
    (net (code "41") (name "IO47") (class "Default")
      (node (ref "LCD1") (pin "7") (pinfunction "D/C_7") (pintype "unspecified"))
      (node (ref "U1") (pin "24") (pinfunction "IO47_24") (pintype "input"))
    )
    (net (code "42") (name "IO48") (class "Default")
      (node (ref "LCD1") (pin "9") (pinfunction "SCL_9") (pintype "unspecified"))
      (node (ref "U1") (pin "25") (pinfunction "IO48_25") (pintype "input"))
    )
    (net (code "43") (name "Net-(D2-A)") (class "Default")
      (node (ref "D2") (pin "2") (pinfunction "A_2") (pintype "input"))
      (node (ref "USB1") (pin "11") (pinfunction "VBUS_11") (pintype "input"))
      (node (ref "USB1") (pin "2") (pinfunction "VBUS_2") (pintype "input"))
    )
    (net (code "44") (name "Net-(LCD1-LEDA)") (class "Default")
      (node (ref "LCD1") (pin "3") (pinfunction "LEDA_3") (pintype "unspecified"))
      (node (ref "R19") (pin "2") (pinfunction "2_2") (pintype "input"))
    )
    (net (code "45") (name "Net-(LCD1-LEDK)") (class "Default")
      (node (ref "LCD1") (pin "2") (pinfunction "LEDK_2") (pintype "unspecified"))
      (node (ref "R18") (pin "2") (pinfunction "2_2") (pintype "input"))
    )
    (net (code "46") (name "Net-(LED1--)") (class "Default")
      (node (ref "LED1") (pin "1") (pinfunction "-_1") (pintype "input"))
      (node (ref "R9") (pin "1") (pinfunction "1_1") (pintype "input"))
    )
    (net (code "47") (name "Net-(LED2-K)") (class "Default")
      (node (ref "LED2") (pin "1") (pinfunction "K_1") (pintype "input"))
      (node (ref "R10") (pin "1") (pinfunction "1_1") (pintype "input"))
    )
    (net (code "48") (name "Net-(LED3-A)") (class "Default")
      (node (ref "LED3") (pin "2") (pinfunction "A_2") (pintype "unspecified"))
      (node (ref "R12") (pin "2") (pinfunction "2_2") (pintype "input"))
    )
    (net (code "49") (name "Net-(Q2-Pad1)") (class "Default")
      (node (ref "Q2") (pin "1") (pinfunction "1_1") (pintype "input"))
      (node (ref "R16") (pin "2") (pinfunction "2_2") (pintype "input"))
      (node (ref "R17") (pin "2") (pinfunction "2_2") (pintype "input"))
    )
    (net (code "50") (name "Net-(Q2-Pad3)") (class "Default")
      (node (ref "Q2") (pin "3") (pinfunction "3_3") (pintype "input"))
      (node (ref "R18") (pin "1") (pinfunction "1_1") (pintype "input"))
    )
    (net (code "51") (name "Net-(R6-Pad1)") (class "Default")
      (node (ref "R6") (pin "1") (pinfunction "1_1") (pintype "input"))
      (node (ref "RST1") (pin "2") (pinfunction "2_2") (pintype "input"))
    )
    (net (code "52") (name "Net-(U2-RXD)") (class "Default")
      (node (ref "R4") (pin "2") (pinfunction "2_2") (pintype "input"))
      (node (ref "U2") (pin "3") (pinfunction "RXD_3") (pintype "input"))
    )
    (net (code "53") (name "Net-(U2-TXD)") (class "Default")
      (node (ref "R3") (pin "2") (pinfunction "2_2") (pintype "input"))
      (node (ref "U2") (pin "2") (pinfunction "TXD_2") (pintype "input"))
    )
    (net (code "54") (name "Net-(U3-CE)") (class "Default")
      (node (ref "R8") (pin "2") (pinfunction "2_2") (pintype "input"))
      (node (ref "U3") (pin "3") (pinfunction "CE_3") (pintype "unspecified"))
    )
    (net (code "55") (name "Net-(U4-CHRG#)") (class "Default")
      (node (ref "R9") (pin "2") (pinfunction "2_2") (pintype "input"))
      (node (ref "U4") (pin "7") (pinfunction "CHRG#_7") (pintype "unspecified"))
    )
    (net (code "56") (name "Net-(U4-PROG)") (class "Default")
      (node (ref "R11") (pin "2") (pinfunction "2_2") (pintype "input"))
      (node (ref "U4") (pin "2") (pinfunction "PROG_2") (pintype "unspecified"))
    )
    (net (code "57") (name "Net-(U4-STDBY#)") (class "Default")
      (node (ref "R10") (pin "2") (pinfunction "2_2") (pintype "input"))
      (node (ref "U4") (pin "6") (pinfunction "STDBY#_6") (pintype "unspecified"))
    )
    (net (code "58") (name "Net-(U5-CTRL)") (class "Default")
      (node (ref "R13") (pin "1") (pinfunction "1_1") (pintype "input"))
      (node (ref "U5") (pin "1") (pinfunction "CTRL_1") (pintype "input"))
    )
    (net (code "59") (name "Net-(USB1-CC1)") (class "Default")
      (node (ref "R2") (pin "1") (pinfunction "1_1") (pintype "input"))
      (node (ref "USB1") (pin "4") (pinfunction "CC1_4") (pintype "input"))
    )
    (net (code "60") (name "Net-(USB1-CC2)") (class "Default")
      (node (ref "R1") (pin "1") (pinfunction "1_1") (pintype "input"))
      (node (ref "USB1") (pin "10") (pinfunction "CC2_10") (pintype "input"))
    )
    (net (code "61") (name "RTS") (class "Default")
      (node (ref "Q1") (pin "1") (pinfunction "E_1") (pintype "input"))
      (node (ref "Q1") (pin "5") (pinfunction "B_5") (pintype "input"))
      (node (ref "U2") (pin "14") (pinfunction "RTS#_14") (pintype "input"))
    )
    (net (code "62") (name "RXD") (class "Default")
      (node (ref "R3") (pin "1") (pinfunction "1_1") (pintype "input"))
      (node (ref "U1") (pin "36") (pinfunction "RXD0_36") (pintype "input"))
    )
    (net (code "63") (name "TXD") (class "Default")
      (node (ref "R4") (pin "1") (pinfunction "1_1") (pintype "input"))
      (node (ref "U1") (pin "37") (pinfunction "TXD0_37") (pintype "input"))
    )
    (net (code "64") (name "VBUS") (class "Default")
      (node (ref "C6") (pin "1") (pinfunction "1_1") (pintype "input"))
      (node (ref "D2") (pin "1") (pinfunction "K_1") (pintype "input"))
      (node (ref "LED1") (pin "2") (pinfunction "+_2") (pintype "input"))
      (node (ref "LED2") (pin "2") (pinfunction "A_2") (pintype "input"))
      (node (ref "U4") (pin "4") (pinfunction "VCC_4") (pintype "unspecified"))
      (node (ref "U4") (pin "8") (pinfunction "CE_8") (pintype "unspecified"))
    )
    (net (code "65") (name "VCC") (class "Default")
      (node (ref "C1") (pin "1") (pinfunction "1_1") (pintype "unspecified"))
      (node (ref "C3") (pin "1") (pinfunction "1_1") (pintype "input"))
      (node (ref "C4") (pin "1") (pinfunction "1_1") (pintype "unspecified"))
      (node (ref "C5") (pin "2") (pinfunction "2_2") (pintype "input"))
      (node (ref "C7") (pin "2") (pinfunction "2_2") (pintype "input"))
      (node (ref "C8") (pin "2") (pinfunction "2_2") (pintype "unspecified"))
      (node (ref "C9") (pin "2") (pinfunction "2_2") (pintype "input"))
      (node (ref "CARD1") (pin "4") (pinfunction "VDD_4") (pintype "input"))
      (node (ref "LCD1") (pin "4") (pinfunction "VCC_4") (pintype "unspecified"))
      (node (ref "R13") (pin "2") (pinfunction "2_2") (pintype "input"))
      (node (ref "R16") (pin "1") (pinfunction "1_1") (pintype "input"))
      (node (ref "R19") (pin "1") (pinfunction "1_1") (pintype "input"))
      (node (ref "R5") (pin "2") (pinfunction "2_2") (pintype "input"))
      (node (ref "R7") (pin "1") (pinfunction "1_1") (pintype "input"))
      (node (ref "U1") (pin "2") (pinfunction "3V3_2") (pintype "input"))
      (node (ref "U2") (pin "16") (pinfunction "VCC_16") (pintype "input"))
      (node (ref "U2") (pin "4") (pinfunction "V3_4") (pintype "input"))
      (node (ref "U3") (pin "5") (pinfunction "OUT_5") (pintype "unspecified"))
      (node (ref "U5") (pin "6") (pinfunction "VDD_6") (pintype "input"))
    )
    (net (code "66") (name "unconnected-(CARD1-CARD_DET-Pad9)") (class "Default")
      (node (ref "CARD1") (pin "9") (pinfunction "CARD_DET_9") (pintype "input+no_connect"))
    )
    (net (code "67") (name "unconnected-(CARD1-DAT1-Pad8)") (class "Default")
      (node (ref "CARD1") (pin "8") (pinfunction "DAT1_8") (pintype "input+no_connect"))
    )
    (net (code "68") (name "unconnected-(CARD1-DAT2-Pad1)") (class "Default")
      (node (ref "CARD1") (pin "1") (pinfunction "DAT2_1") (pintype "input+no_connect"))
    )
    (net (code "69") (name "unconnected-(SW1-Pad1)") (class "Default")
      (node (ref "SW1") (pin "1") (pinfunction "1_1") (pintype "unspecified+no_connect"))
    )
    (net (code "70") (name "unconnected-(SW1-Pad4)") (class "Default")
      (node (ref "SW1") (pin "4") (pinfunction "4_4") (pintype "unspecified+no_connect"))
    )
    (net (code "71") (name "unconnected-(SW1-Pad5)") (class "Default")
      (node (ref "SW1") (pin "5") (pinfunction "5_5") (pintype "unspecified+no_connect"))
    )
    (net (code "72") (name "unconnected-(U1-IO35-Pad28)") (class "Default")
      (node (ref "U1") (pin "28") (pinfunction "IO35_28") (pintype "input+no_connect"))
    )
    (net (code "73") (name "unconnected-(U1-IO36-Pad29)") (class "Default")
      (node (ref "U1") (pin "29") (pinfunction "IO36_29") (pintype "input+no_connect"))
    )
    (net (code "74") (name "unconnected-(U1-IO37-Pad30)") (class "Default")
      (node (ref "U1") (pin "30") (pinfunction "IO37_30") (pintype "input+no_connect"))
    )
    (net (code "75") (name "unconnected-(U2-CTS#-Pad9)") (class "Default")
      (node (ref "U2") (pin "9") (pinfunction "CTS#_9") (pintype "input+no_connect"))
    )
    (net (code "76") (name "unconnected-(U2-DCD#-Pad12)") (class "Default")
      (node (ref "U2") (pin "12") (pinfunction "DCD#_12") (pintype "input+no_connect"))
    )
    (net (code "77") (name "unconnected-(U2-DSR#-Pad10)") (class "Default")
      (node (ref "U2") (pin "10") (pinfunction "DSR#_10") (pintype "input+no_connect"))
    )
    (net (code "78") (name "unconnected-(U2-NC.-Pad7)") (class "Default")
      (node (ref "U2") (pin "7") (pinfunction "NC._7") (pintype "input+no_connect"))
    )
    (net (code "79") (name "unconnected-(U2-NC.-Pad8)") (class "Default")
      (node (ref "U2") (pin "8") (pinfunction "NC._8") (pintype "input+no_connect"))
    )
    (net (code "80") (name "unconnected-(U2-R232-Pad15)") (class "Default")
      (node (ref "U2") (pin "15") (pinfunction "R232_15") (pintype "input+no_connect"))
    )
    (net (code "81") (name "unconnected-(U2-RI#-Pad11)") (class "Default")
      (node (ref "U2") (pin "11") (pinfunction "RI#_11") (pintype "input+no_connect"))
    )
    (net (code "82") (name "unconnected-(U3-NC-Pad4)") (class "Default")
      (node (ref "U3") (pin "4") (pinfunction "NC_4") (pintype "unspecified+no_connect"))
    )
    (net (code "83") (name "unconnected-(U4-EP-Pad9)") (class "Default")
      (node (ref "U4") (pin "9") (pinfunction "EP_9") (pintype "unspecified+no_connect"))
    )
    (net (code "84") (name "unconnected-(USB1-SBU1-Pad9)") (class "Default")
      (node (ref "USB1") (pin "9") (pinfunction "SBU1_9") (pintype "input+no_connect"))
    )
    (net (code "85") (name "unconnected-(USB1-SBU2-Pad3)") (class "Default")
      (node (ref "USB1") (pin "3") (pinfunction "SBU2_3") (pintype "input+no_connect"))
    )
  )
)
